# HeadsetR1.net
KiCad netlist of a schematic drawn in EAGLE
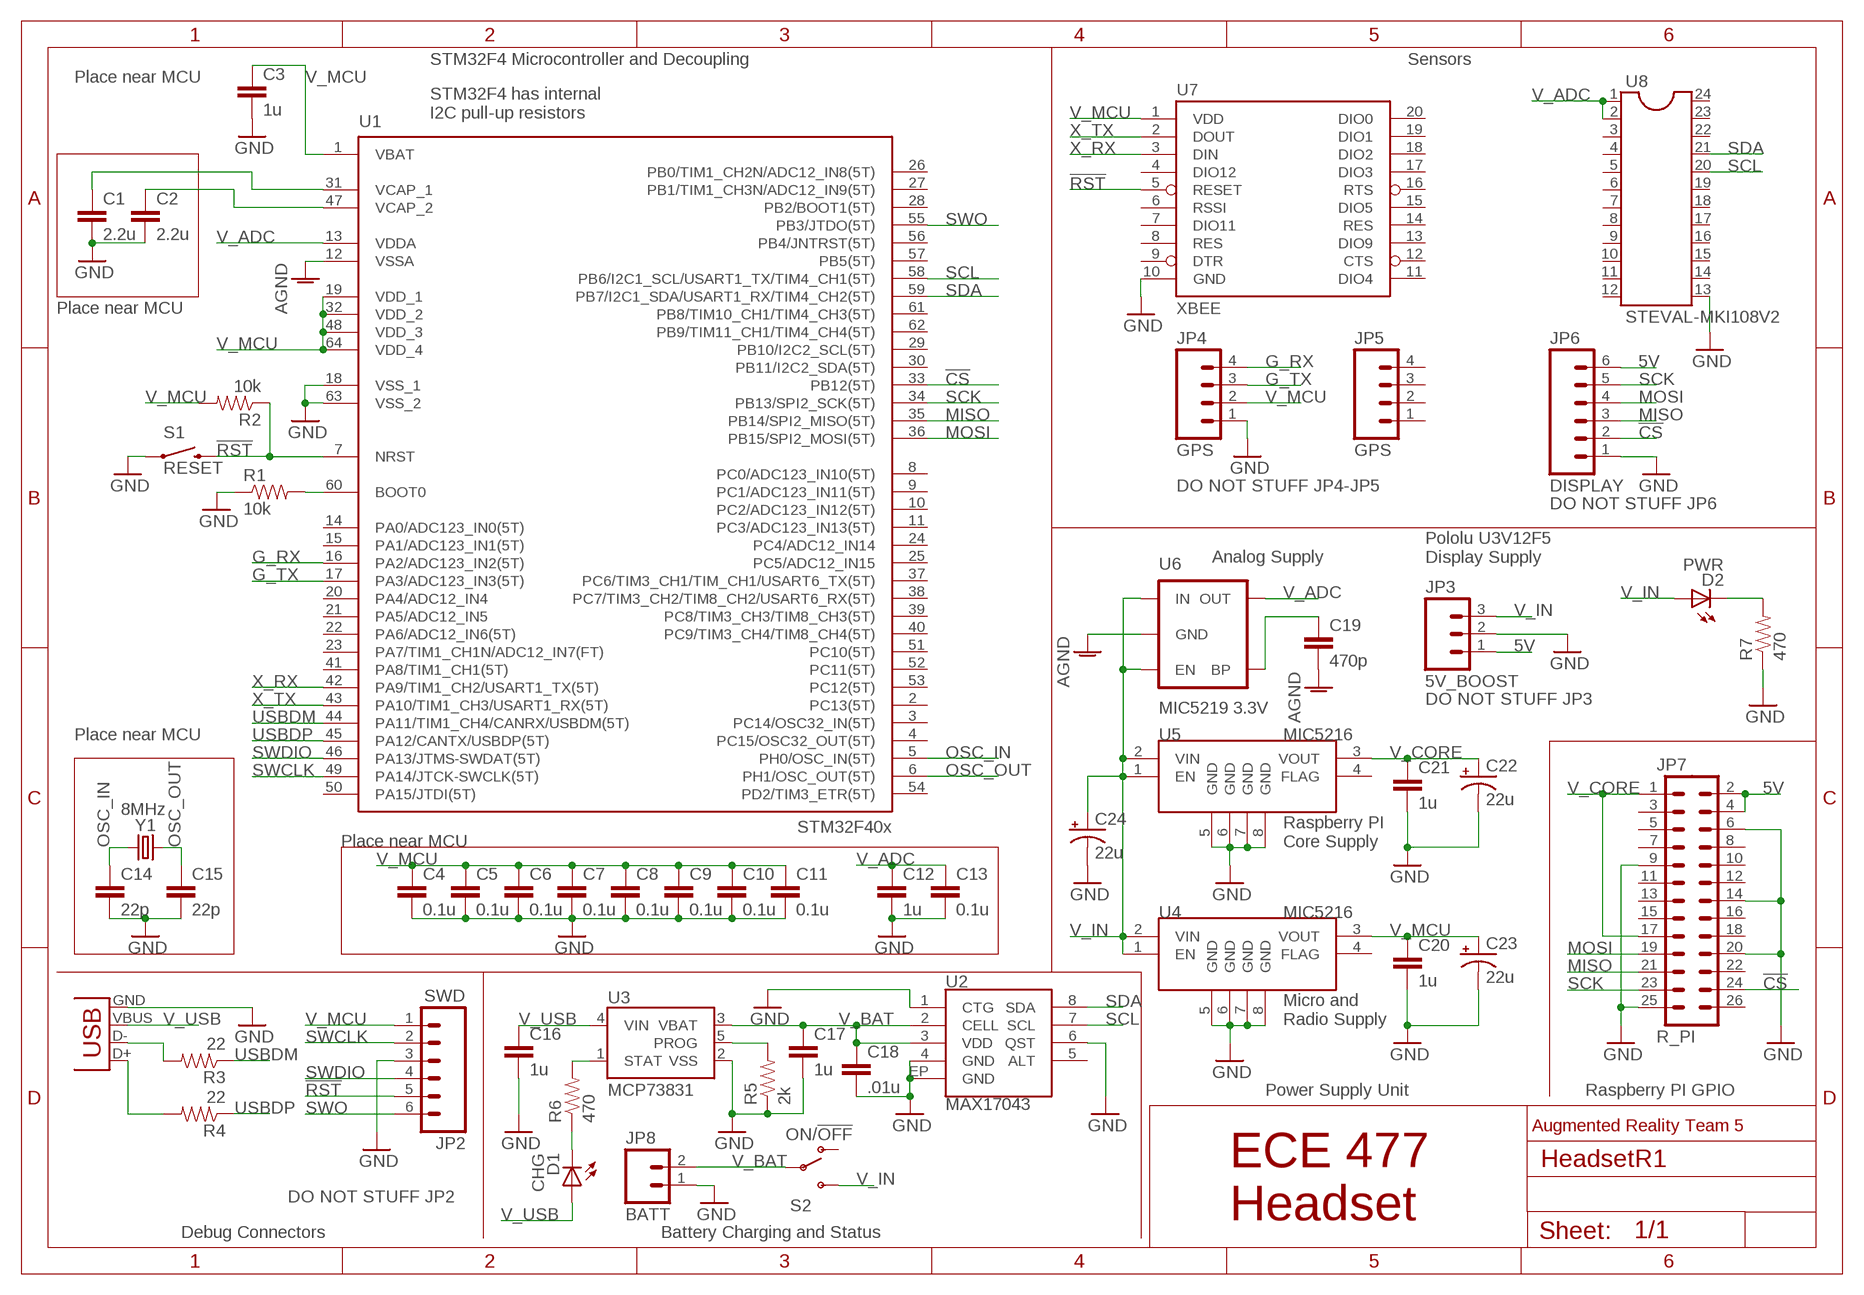
[diagram p0: schematic, sheet 1]

(export (version "E")
  (design (tool "Eeschema 10.0.6"))
  (components
    (comp (ref "C1")
      (value "2.2u")
      (footprint "eagle-import:0805")
      (libsource (lib "eagle-import") (part "CAP0805"))
    )
    (comp (ref "C2")
      (value "2.2u")
      (footprint "eagle-import:0805")
      (libsource (lib "eagle-import") (part "CAP0805"))
    )
    (comp (ref "C3")
      (value "1u")
      (footprint "eagle-import:0805")
      (libsource (lib "eagle-import") (part "CAP0805"))
    )
    (comp (ref "C4")
      (value "0.1u")
      (footprint "eagle-import:0805")
      (libsource (lib "eagle-import") (part "CAP0805"))
    )
    (comp (ref "C5")
      (value "0.1u")
      (footprint "eagle-import:0805")
      (libsource (lib "eagle-import") (part "CAP0805"))
    )
    (comp (ref "C6")
      (value "0.1u")
      (footprint "eagle-import:0805")
      (libsource (lib "eagle-import") (part "CAP0805"))
    )
    (comp (ref "C7")
      (value "0.1u")
      (footprint "eagle-import:0805")
      (libsource (lib "eagle-import") (part "CAP0805"))
    )
    (comp (ref "C8")
      (value "0.1u")
      (footprint "eagle-import:0805")
      (libsource (lib "eagle-import") (part "CAP0805"))
    )
    (comp (ref "C9")
      (value "0.1u")
      (footprint "eagle-import:0805")
      (libsource (lib "eagle-import") (part "CAP0805"))
    )
    (comp (ref "C10")
      (value "0.1u")
      (footprint "eagle-import:0805")
      (libsource (lib "eagle-import") (part "CAP0805"))
    )
    (comp (ref "C11")
      (value "0.1u")
      (footprint "eagle-import:0805")
      (libsource (lib "eagle-import") (part "CAP0805"))
    )
    (comp (ref "C12")
      (value "1u")
      (footprint "eagle-import:0805")
      (libsource (lib "eagle-import") (part "CAP0805"))
    )
    (comp (ref "C13")
      (value "0.1u")
      (footprint "eagle-import:0805")
      (libsource (lib "eagle-import") (part "CAP0805"))
    )
    (comp (ref "C14")
      (value "22p")
      (footprint "eagle-import:0805")
      (libsource (lib "eagle-import") (part "CAP0805"))
    )
    (comp (ref "C15")
      (value "22p")
      (footprint "eagle-import:0805")
      (libsource (lib "eagle-import") (part "CAP0805"))
    )
    (comp (ref "C16")
      (value "1u")
      (footprint "eagle-import:0805")
      (libsource (lib "eagle-import") (part "CAP0805"))
    )
    (comp (ref "C17")
      (value "1u")
      (footprint "eagle-import:0805")
      (libsource (lib "eagle-import") (part "CAP0805"))
    )
    (comp (ref "C18")
      (value ".01u")
      (footprint "eagle-import:0805")
      (libsource (lib "eagle-import") (part "CAP0805"))
    )
    (comp (ref "C19")
      (value "470p")
      (footprint "eagle-import:0805")
      (libsource (lib "eagle-import") (part "CAP0805"))
    )
    (comp (ref "C20")
      (value "1u")
      (footprint "eagle-import:0805")
      (libsource (lib "eagle-import") (part "CAP0805"))
    )
    (comp (ref "C21")
      (value "1u")
      (footprint "eagle-import:0805")
      (libsource (lib "eagle-import") (part "CAP0805"))
    )
    (comp (ref "C22")
      (value "22u")
      (footprint "eagle-import:VISHAY_D")
      (libsource (lib "eagle-import") (part "CAP_POLVISHAY_D"))
    )
    (comp (ref "C23")
      (value "22u")
      (footprint "eagle-import:VISHAY_D")
      (libsource (lib "eagle-import") (part "CAP_POLVISHAY_D"))
    )
    (comp (ref "C24")
      (value "22u")
      (footprint "eagle-import:VISHAY_D")
      (libsource (lib "eagle-import") (part "CAP_POLVISHAY_D"))
    )
    (comp (ref "D1")
      (value "CHG")
      (footprint "eagle-import:LED-1206")
      (libsource (lib "eagle-import") (part "LED-RED1206"))
    )
    (comp (ref "D2")
      (value "PWR")
      (footprint "eagle-import:LED-1206")
      (libsource (lib "eagle-import") (part "LED-RED1206"))
    )
    (comp (ref "JP1")
      (value "USBSMD")
      (footprint "eagle-import:USB-MINIB")
      (libsource (lib "eagle-import") (part "USBSMD"))
    )
    (comp (ref "JP2")
      (value "SWD")
      (footprint "eagle-import:1X06")
      (libsource (lib "eagle-import") (part "M06SIP"))
    )
    (comp (ref "JP3")
      (value "5V_BOOST")
      (footprint "eagle-import:1X03")
      (libsource (lib "eagle-import") (part "M03PTH"))
    )
    (comp (ref "JP4")
      (value "GPS")
      (footprint "eagle-import:1X04")
      (libsource (lib "eagle-import") (part "M04PTH"))
    )
    (comp (ref "JP5")
      (value "GPS")
      (footprint "eagle-import:1X04")
      (libsource (lib "eagle-import") (part "M04PTH"))
    )
    (comp (ref "JP6")
      (value "DISPLAY")
      (footprint "eagle-import:1X06")
      (libsource (lib "eagle-import") (part "M06SIP"))
    )
    (comp (ref "JP7")
      (value "R_PI")
      (footprint "eagle-import:2X13")
      (libsource (lib "eagle-import") (part "M13X22X13"))
    )
    (comp (ref "JP8")
      (value "BATT")
      (footprint "eagle-import:JST-2-PTH")
      (libsource (lib "eagle-import") (part "M02JST-PTH-2"))
    )
    (comp (ref "R1")
      (value "10k")
      (footprint "eagle-import:0805")
      (libsource (lib "eagle-import") (part "RES"))
    )
    (comp (ref "R2")
      (value "10k")
      (footprint "eagle-import:0805")
      (libsource (lib "eagle-import") (part "RES"))
    )
    (comp (ref "R3")
      (value "22")
      (footprint "eagle-import:0805")
      (libsource (lib "eagle-import") (part "RES"))
    )
    (comp (ref "R4")
      (value "22")
      (footprint "eagle-import:0805")
      (libsource (lib "eagle-import") (part "RES"))
    )
    (comp (ref "R5")
      (value "2k")
      (footprint "eagle-import:0805")
      (libsource (lib "eagle-import") (part "RES"))
    )
    (comp (ref "R6")
      (value "470")
      (footprint "eagle-import:0805")
      (libsource (lib "eagle-import") (part "RES"))
    )
    (comp (ref "R7")
      (value "470")
      (footprint "eagle-import:0805")
      (libsource (lib "eagle-import") (part "RES"))
    )
    (comp (ref "S1")
      (value "RESET")
      (footprint "eagle-import:TACTILE-PTH")
      (libsource (lib "eagle-import") (part "SWITCH-MOMENTARY-2PTH"))
    )
    (comp (ref "S2")
      (value "ON/!OFF!")
      (footprint "eagle-import:SWITCH-SPDT")
      (libsource (lib "eagle-import") (part "SWITCH-SPDTPTH"))
    )
    (comp (ref "U1")
      (value "STM32F405RGT6")
      (footprint "eagle-import:TQFP64")
      (libsource (lib "eagle-import") (part "STM32F405R"))
    )
    (comp (ref "U2")
      (value "MAX17043")
      (footprint "eagle-import:TDFN-8")
      (libsource (lib "eagle-import") (part "MAX1704X"))
    )
    (comp (ref "U3")
      (value "MCP73831")
      (footprint "eagle-import:SOT23-5")
      (libsource (lib "eagle-import") (part "MCP73831"))
    )
    (comp (ref "U4")
      (value "MIC5216")
      (footprint "eagle-import:MSOP8")
      (libsource (lib "eagle-import") (part "V_REG_MIC5216"))
    )
    (comp (ref "U5")
      (value "MIC5216")
      (footprint "eagle-import:MSOP8")
      (libsource (lib "eagle-import") (part "V_REG_MIC5216"))
    )
    (comp (ref "U6")
      (value "MIC5219 3.3V")
      (footprint "eagle-import:SOT23-5")
      (libsource (lib "eagle-import") (part "V_REG_MIC52193.3V"))
    )
    (comp (ref "U7")
      (value "XBEE")
      (footprint "eagle-import:XBEE-1")
      (libsource (lib "eagle-import") (part "XBEE-1B1"))
    )
    (comp (ref "U8")
      (value "STEVAL-MKI108V2")
      (footprint "eagle-import:DIL24-6")
      (libsource (lib "eagle-import") (part "DIL24-6"))
    )
    (comp (ref "Y1")
      (value "8MHz")
      (footprint "eagle-import:HC49UP")
      (libsource (lib "eagle-import") (part "CRYSTALSMD"))
    )
  )
  (nets
    (net (code "1") (name "/5V") (class "Default")
      (node (ref "JP3") (pin "1") (pinfunction "1_1") (pintype "passive"))
      (node (ref "JP6") (pin "6") (pinfunction "6_6") (pintype "passive"))
      (node (ref "JP7") (pin "2") (pinfunction "2_2") (pintype "passive"))
      (node (ref "JP7") (pin "4") (pinfunction "4_4") (pintype "passive"))
    )
    (net (code "2") (name "/G_RX") (class "Default")
      (node (ref "JP4") (pin "4") (pinfunction "4_4") (pintype "passive"))
      (node (ref "U1") (pin "16") (pinfunction "PA2/ADC123_IN2(5T)_16") (pintype "bidirectional"))
    )
    (net (code "3") (name "/G_TX") (class "Default")
      (node (ref "JP4") (pin "3") (pinfunction "3_3") (pintype "passive"))
      (node (ref "U1") (pin "17") (pinfunction "PA3/ADC123_IN3(5T)_17") (pintype "bidirectional"))
    )
    (net (code "4") (name "/MISO") (class "Default")
      (node (ref "JP6") (pin "3") (pinfunction "3_3") (pintype "passive"))
      (node (ref "JP7") (pin "21") (pinfunction "21_21") (pintype "passive"))
      (node (ref "U1") (pin "35") (pinfunction "PB14/SPI2_MISO(5T)_35") (pintype "bidirectional"))
    )
    (net (code "5") (name "/MOSI") (class "Default")
      (node (ref "JP6") (pin "4") (pinfunction "4_4") (pintype "passive"))
      (node (ref "JP7") (pin "19") (pinfunction "19_19") (pintype "passive"))
      (node (ref "U1") (pin "36") (pinfunction "PB15/SPI2_MOSI(5T)_36") (pintype "bidirectional"))
    )
    (net (code "6") (name "/OSC_IN") (class "Default")
      (node (ref "C14") (pin "1") (pinfunction "1_1") (pintype "passive"))
      (node (ref "U1") (pin "5") (pinfunction "PH0/OSC_IN(5T)_5") (pintype "bidirectional"))
      (node (ref "Y1") (pin "1") (pinfunction "1_1") (pintype "passive"))
    )
    (net (code "7") (name "/OSC_OUT") (class "Default")
      (node (ref "C15") (pin "1") (pinfunction "1_1") (pintype "passive"))
      (node (ref "U1") (pin "6") (pinfunction "PH1/OSC_OUT(5T)_6") (pintype "bidirectional"))
      (node (ref "Y1") (pin "2") (pinfunction "2_2") (pintype "passive"))
    )
    (net (code "8") (name "/SCK") (class "Default")
      (node (ref "JP6") (pin "5") (pinfunction "5_5") (pintype "passive"))
      (node (ref "JP7") (pin "23") (pinfunction "23_23") (pintype "passive"))
      (node (ref "U1") (pin "34") (pinfunction "PB13/SPI2_SCK(5T)_34") (pintype "bidirectional"))
    )
    (net (code "9") (name "/SCL") (class "Default")
      (node (ref "U1") (pin "58") (pinfunction "PB6/I2C1_SCL/USART1_TX/TIM4_CH1(5T)_58") (pintype "bidirectional"))
      (node (ref "U2") (pin "7") (pinfunction "SCL_7") (pintype "bidirectional"))
      (node (ref "U8") (pin "20") (pinfunction "20_20") (pintype "passive"))
    )
    (net (code "10") (name "/SDA") (class "Default")
      (node (ref "U1") (pin "59") (pinfunction "PB7/I2C1_SDA/USART1_RX/TIM4_CH2(5T)_59") (pintype "bidirectional"))
      (node (ref "U2") (pin "8") (pinfunction "SDA_8") (pintype "bidirectional"))
      (node (ref "U8") (pin "21") (pinfunction "21_21") (pintype "passive"))
    )
    (net (code "11") (name "/SWCLK") (class "Default")
      (node (ref "JP2") (pin "2") (pinfunction "2_2") (pintype "passive"))
      (node (ref "U1") (pin "49") (pinfunction "PA14/JTCK-SWCLK(5T)_49") (pintype "bidirectional"))
    )
    (net (code "12") (name "/SWDIO") (class "Default")
      (node (ref "JP2") (pin "4") (pinfunction "4_4") (pintype "passive"))
      (node (ref "U1") (pin "46") (pinfunction "PA13/JTMS-SWDAT(5T)_46") (pintype "bidirectional"))
    )
    (net (code "13") (name "/SWO") (class "Default")
      (node (ref "JP2") (pin "6") (pinfunction "6_6") (pintype "passive"))
      (node (ref "U1") (pin "55") (pinfunction "PB3/JTDO(5T)_55") (pintype "bidirectional"))
    )
    (net (code "14") (name "/USBDM") (class "Default")
      (node (ref "R3") (pin "1") (pinfunction "1_1") (pintype "passive"))
      (node (ref "U1") (pin "44") (pinfunction "PA11/TIM1_CH4/CANRX/USBDM(5T)_44") (pintype "bidirectional"))
    )
    (net (code "15") (name "/USBDP") (class "Default")
      (node (ref "R4") (pin "1") (pinfunction "1_1") (pintype "passive"))
      (node (ref "U1") (pin "45") (pinfunction "PA12/CANTX/USBDP(5T)_45") (pintype "bidirectional"))
    )
    (net (code "16") (name "/V_ADC") (class "Default")
      (node (ref "C12") (pin "1") (pinfunction "1_1") (pintype "passive"))
      (node (ref "C13") (pin "1") (pinfunction "1_1") (pintype "passive"))
      (node (ref "U1") (pin "13") (pinfunction "VDDA_13") (pintype "bidirectional"))
      (node (ref "U6") (pin "5") (pinfunction "OUT_5") (pintype "passive"))
      (node (ref "U8") (pin "1") (pinfunction "1_1") (pintype "passive"))
      (node (ref "U8") (pin "2") (pinfunction "2_2") (pintype "passive"))
    )
    (net (code "17") (name "/V_BAT") (class "Default")
      (node (ref "C17") (pin "1") (pinfunction "1_1") (pintype "passive"))
      (node (ref "C18") (pin "1") (pinfunction "1_1") (pintype "passive"))
      (node (ref "JP8") (pin "2") (pinfunction "2_2") (pintype "passive"))
      (node (ref "S2") (pin "2") (pinfunction "P_2") (pintype "passive"))
      (node (ref "U2") (pin "2") (pinfunction "CELL_2") (pintype "bidirectional"))
      (node (ref "U2") (pin "3") (pinfunction "VDD_3") (pintype "bidirectional"))
      (node (ref "U3") (pin "3") (pinfunction "VBAT_3") (pintype "power_in"))
    )
    (net (code "18") (name "/V_CORE") (class "Default")
      (node (ref "C21") (pin "1") (pinfunction "1_1") (pintype "passive"))
      (node (ref "C22") (pin "+") (pinfunction "+_+") (pintype "passive"))
      (node (ref "JP7") (pin "1") (pinfunction "1_1") (pintype "passive"))
      (node (ref "JP7") (pin "17") (pinfunction "17_17") (pintype "passive"))
      (node (ref "U5") (pin "3") (pinfunction "VOUT_3") (pintype "bidirectional"))
    )
    (net (code "19") (name "/V_IN") (class "Default")
      (node (ref "C24") (pin "+") (pinfunction "+_+") (pintype "passive"))
      (node (ref "D2") (pin "A") (pinfunction "A_A") (pintype "passive"))
      (node (ref "JP3") (pin "3") (pinfunction "3_3") (pintype "passive"))
      (node (ref "S2") (pin "3") (pinfunction "S_3") (pintype "passive"))
      (node (ref "U4") (pin "1") (pinfunction "EN_1") (pintype "bidirectional"))
      (node (ref "U4") (pin "2") (pinfunction "VIN_2") (pintype "bidirectional"))
      (node (ref "U5") (pin "1") (pinfunction "EN_1") (pintype "bidirectional"))
      (node (ref "U5") (pin "2") (pinfunction "VIN_2") (pintype "bidirectional"))
      (node (ref "U6") (pin "1") (pinfunction "IN_1") (pintype "input"))
      (node (ref "U6") (pin "3") (pinfunction "EN_3") (pintype "input"))
    )
    (net (code "20") (name "/V_MCU") (class "Default")
      (node (ref "C10") (pin "1") (pinfunction "1_1") (pintype "passive"))
      (node (ref "C11") (pin "1") (pinfunction "1_1") (pintype "passive"))
      (node (ref "C20") (pin "1") (pinfunction "1_1") (pintype "passive"))
      (node (ref "C23") (pin "+") (pinfunction "+_+") (pintype "passive"))
      (node (ref "C3") (pin "1") (pinfunction "1_1") (pintype "passive"))
      (node (ref "C4") (pin "1") (pinfunction "1_1") (pintype "passive"))
      (node (ref "C5") (pin "1") (pinfunction "1_1") (pintype "passive"))
      (node (ref "C6") (pin "1") (pinfunction "1_1") (pintype "passive"))
      (node (ref "C7") (pin "1") (pinfunction "1_1") (pintype "passive"))
      (node (ref "C8") (pin "1") (pinfunction "1_1") (pintype "passive"))
      (node (ref "C9") (pin "1") (pinfunction "1_1") (pintype "passive"))
      (node (ref "JP2") (pin "1") (pinfunction "1_1") (pintype "passive"))
      (node (ref "JP4") (pin "2") (pinfunction "2_2") (pintype "passive"))
      (node (ref "R2") (pin "2") (pinfunction "2_2") (pintype "passive"))
      (node (ref "U1") (pin "1") (pinfunction "VBAT_1") (pintype "bidirectional"))
      (node (ref "U1") (pin "19") (pinfunction "VDD_1_19") (pintype "bidirectional"))
      (node (ref "U1") (pin "32") (pinfunction "VDD_2_32") (pintype "bidirectional"))
      (node (ref "U1") (pin "48") (pinfunction "VDD_3_48") (pintype "bidirectional"))
      (node (ref "U1") (pin "64") (pinfunction "VDD_4_64") (pintype "bidirectional"))
      (node (ref "U4") (pin "3") (pinfunction "VOUT_3") (pintype "bidirectional"))
      (node (ref "U7") (pin "1") (pinfunction "VDD_1") (pintype "power_in"))
    )
    (net (code "21") (name "/V_USB") (class "Default")
      (node (ref "C16") (pin "1") (pinfunction "1_1") (pintype "passive"))
      (node (ref "D1") (pin "A") (pinfunction "A_A") (pintype "passive"))
      (node (ref "JP1") (pin "VBUS") (pinfunction "VBUS_VBUS") (pintype "bidirectional"))
      (node (ref "U3") (pin "4") (pinfunction "VIN_4") (pintype "power_in"))
    )
    (net (code "22") (name "/X_RX") (class "Default")
      (node (ref "U1") (pin "42") (pinfunction "PA9/TIM1_CH2/USART1_TX(5T)_42") (pintype "bidirectional"))
      (node (ref "U7") (pin "3") (pinfunction "DIN_3") (pintype "input"))
    )
    (net (code "23") (name "/X_TX") (class "Default")
      (node (ref "U1") (pin "43") (pinfunction "PA10/TIM1_CH3/USART1_RX(5T)_43") (pintype "bidirectional"))
      (node (ref "U7") (pin "2") (pinfunction "DOUT_2") (pintype "output"))
    )
    (net (code "24") (name "/~{CS}") (class "Default")
      (node (ref "JP6") (pin "2") (pinfunction "2_2") (pintype "passive"))
      (node (ref "JP7") (pin "24") (pinfunction "24_24") (pintype "passive"))
      (node (ref "U1") (pin "33") (pinfunction "PB12(5T)_33") (pintype "bidirectional"))
    )
    (net (code "25") (name "/~{RST}") (class "Default")
      (node (ref "JP2") (pin "5") (pinfunction "5_5") (pintype "passive"))
      (node (ref "R2") (pin "1") (pinfunction "1_1") (pintype "passive"))
      (node (ref "S1") (pin "3") (pinfunction "2_3") (pintype "passive"))
      (node (ref "U1") (pin "7") (pinfunction "NRST_7") (pintype "bidirectional"))
      (node (ref "U7") (pin "5") (pinfunction "RESET_5") (pintype "input"))
    )
    (net (code "26") (name "AGND") (class "Default")
      (node (ref "C19") (pin "2") (pinfunction "2_2") (pintype "passive"))
      (node (ref "U1") (pin "12") (pinfunction "VSSA_12") (pintype "bidirectional"))
      (node (ref "U6") (pin "2") (pinfunction "GND_2") (pintype "input"))
    )
    (net (code "27") (name "GND") (class "Default")
      (node (ref "C1") (pin "2") (pinfunction "2_2") (pintype "passive"))
      (node (ref "C10") (pin "2") (pinfunction "2_2") (pintype "passive"))
      (node (ref "C11") (pin "2") (pinfunction "2_2") (pintype "passive"))
      (node (ref "C12") (pin "2") (pinfunction "2_2") (pintype "passive"))
      (node (ref "C13") (pin "2") (pinfunction "2_2") (pintype "passive"))
      (node (ref "C14") (pin "2") (pinfunction "2_2") (pintype "passive"))
      (node (ref "C15") (pin "2") (pinfunction "2_2") (pintype "passive"))
      (node (ref "C16") (pin "2") (pinfunction "2_2") (pintype "passive"))
      (node (ref "C17") (pin "2") (pinfunction "2_2") (pintype "passive"))
      (node (ref "C18") (pin "2") (pinfunction "2_2") (pintype "passive"))
      (node (ref "C2") (pin "2") (pinfunction "2_2") (pintype "passive"))
      (node (ref "C20") (pin "2") (pinfunction "2_2") (pintype "passive"))
      (node (ref "C21") (pin "2") (pinfunction "2_2") (pintype "passive"))
      (node (ref "C22") (pin "-") (pinfunction "-_-") (pintype "passive"))
      (node (ref "C23") (pin "-") (pinfunction "-_-") (pintype "passive"))
      (node (ref "C24") (pin "-") (pinfunction "-_-") (pintype "passive"))
      (node (ref "C3") (pin "2") (pinfunction "2_2") (pintype "passive"))
      (node (ref "C4") (pin "2") (pinfunction "2_2") (pintype "passive"))
      (node (ref "C5") (pin "2") (pinfunction "2_2") (pintype "passive"))
      (node (ref "C6") (pin "2") (pinfunction "2_2") (pintype "passive"))
      (node (ref "C7") (pin "2") (pinfunction "2_2") (pintype "passive"))
      (node (ref "C8") (pin "2") (pinfunction "2_2") (pintype "passive"))
      (node (ref "C9") (pin "2") (pinfunction "2_2") (pintype "passive"))
      (node (ref "JP1") (pin "GND") (pinfunction "GND_GND") (pintype "bidirectional"))
      (node (ref "JP2") (pin "3") (pinfunction "3_3") (pintype "passive"))
      (node (ref "JP3") (pin "2") (pinfunction "2_2") (pintype "passive"))
      (node (ref "JP4") (pin "1") (pinfunction "1_1") (pintype "passive"))
      (node (ref "JP6") (pin "1") (pinfunction "1_1") (pintype "passive"))
      (node (ref "JP7") (pin "14") (pinfunction "14_14") (pintype "passive"))
      (node (ref "JP7") (pin "20") (pinfunction "20_20") (pintype "passive"))
      (node (ref "JP7") (pin "25") (pinfunction "25_25") (pintype "passive"))
      (node (ref "JP7") (pin "6") (pinfunction "6_6") (pintype "passive"))
      (node (ref "JP7") (pin "9") (pinfunction "9_9") (pintype "passive"))
      (node (ref "JP8") (pin "1") (pinfunction "1_1") (pintype "passive"))
      (node (ref "R1") (pin "1") (pinfunction "1_1") (pintype "passive"))
      (node (ref "R5") (pin "1") (pinfunction "1_1") (pintype "passive"))
      (node (ref "R7") (pin "1") (pinfunction "1_1") (pintype "passive"))
      (node (ref "S1") (pin "1") (pinfunction "1_1") (pintype "passive"))
      (node (ref "U1") (pin "18") (pinfunction "VSS_1_18") (pintype "bidirectional"))
      (node (ref "U1") (pin "63") (pinfunction "VSS_2_63") (pintype "bidirectional"))
      (node (ref "U2") (pin "1") (pinfunction "CTG_1") (pintype "bidirectional"))
      (node (ref "U2") (pin "4") (pinfunction "GND_4") (pintype "bidirectional"))
      (node (ref "U2") (pin "6") (pinfunction "QST_6") (pintype "bidirectional"))
      (node (ref "U2") (pin "EP") (pinfunction "GND_EP") (pintype "bidirectional"))
      (node (ref "U3") (pin "2") (pinfunction "VSS_2") (pintype "power_in"))
      (node (ref "U4") (pin "5") (pinfunction "GND_5") (pintype "bidirectional"))
      (node (ref "U4") (pin "6") (pinfunction "GND_6") (pintype "bidirectional"))
      (node (ref "U4") (pin "7") (pinfunction "GND_7") (pintype "bidirectional"))
      (node (ref "U4") (pin "8") (pinfunction "GND_8") (pintype "bidirectional"))
      (node (ref "U5") (pin "5") (pinfunction "GND_5") (pintype "bidirectional"))
      (node (ref "U5") (pin "6") (pinfunction "GND_6") (pintype "bidirectional"))
      (node (ref "U5") (pin "7") (pinfunction "GND_7") (pintype "bidirectional"))
      (node (ref "U5") (pin "8") (pinfunction "GND_8") (pintype "bidirectional"))
      (node (ref "U7") (pin "10") (pinfunction "GND_10") (pintype "power_in"))
      (node (ref "U8") (pin "13") (pinfunction "13_13") (pintype "passive"))
    )
    (net (code "28") (name "Net-(D1-PadC)") (class "Default")
      (node (ref "D1") (pin "C") (pinfunction "C_C") (pintype "passive"))
      (node (ref "R6") (pin "1") (pinfunction "1_1") (pintype "passive"))
    )
    (net (code "29") (name "Net-(D2-PadC)") (class "Default")
      (node (ref "D2") (pin "C") (pinfunction "C_C") (pintype "passive"))
      (node (ref "R7") (pin "2") (pinfunction "2_2") (pintype "passive"))
    )
    (net (code "30") (name "Net-(JP1-PadD+)") (class "Default")
      (node (ref "JP1") (pin "D+") (pinfunction "D+_D+") (pintype "bidirectional"))
      (node (ref "R4") (pin "2") (pinfunction "2_2") (pintype "passive"))
    )
    (net (code "31") (name "Net-(JP1-PadD-)") (class "Default")
      (node (ref "JP1") (pin "D-") (pinfunction "D-_D-") (pintype "bidirectional"))
      (node (ref "R3") (pin "2") (pinfunction "2_2") (pintype "passive"))
    )
    (net (code "32") (name "Net-(U1-BOOT0)") (class "Default")
      (node (ref "R1") (pin "2") (pinfunction "2_2") (pintype "passive"))
      (node (ref "U1") (pin "60") (pinfunction "BOOT0_60") (pintype "bidirectional"))
    )
    (net (code "33") (name "Net-(U1-VCAP_1)") (class "Default")
      (node (ref "C1") (pin "1") (pinfunction "1_1") (pintype "passive"))
      (node (ref "U1") (pin "31") (pinfunction "VCAP_1_31") (pintype "bidirectional"))
    )
    (net (code "34") (name "Net-(U1-VCAP_2)") (class "Default")
      (node (ref "C2") (pin "1") (pinfunction "1_1") (pintype "passive"))
      (node (ref "U1") (pin "47") (pinfunction "VCAP_2_47") (pintype "bidirectional"))
    )
    (net (code "35") (name "Net-(U3-PROG)") (class "Default")
      (node (ref "R5") (pin "2") (pinfunction "2_2") (pintype "passive"))
      (node (ref "U3") (pin "5") (pinfunction "PROG_5") (pintype "input"))
    )
    (net (code "36") (name "Net-(U3-STAT)") (class "Default")
      (node (ref "R6") (pin "2") (pinfunction "2_2") (pintype "passive"))
      (node (ref "U3") (pin "1") (pinfunction "STAT_1") (pintype "output"))
    )
    (net (code "37") (name "Net-(U6-BP)") (class "Default")
      (node (ref "C19") (pin "1") (pinfunction "1_1") (pintype "passive"))
      (node (ref "U6") (pin "4") (pinfunction "BP_4") (pintype "input"))
    )
    (net (code "38") (name "unconnected-(JP5-Pad1)") (class "Default")
      (node (ref "JP5") (pin "1") (pinfunction "1_1") (pintype "passive"))
    )
    (net (code "39") (name "unconnected-(JP5-Pad2)") (class "Default")
      (node (ref "JP5") (pin "2") (pinfunction "2_2") (pintype "passive"))
    )
    (net (code "40") (name "unconnected-(JP5-Pad3)") (class "Default")
      (node (ref "JP5") (pin "3") (pinfunction "3_3") (pintype "passive"))
    )
    (net (code "41") (name "unconnected-(JP5-Pad4)") (class "Default")
      (node (ref "JP5") (pin "4") (pinfunction "4_4") (pintype "passive"))
    )
    (net (code "42") (name "unconnected-(JP7-Pad3)") (class "Default")
      (node (ref "JP7") (pin "3") (pinfunction "3_3") (pintype "passive"))
    )
    (net (code "43") (name "unconnected-(JP7-Pad5)") (class "Default")
      (node (ref "JP7") (pin "5") (pinfunction "5_5") (pintype "passive"))
    )
    (net (code "44") (name "unconnected-(JP7-Pad7)") (class "Default")
      (node (ref "JP7") (pin "7") (pinfunction "7_7") (pintype "passive"))
    )
    (net (code "45") (name "unconnected-(JP7-Pad8)") (class "Default")
      (node (ref "JP7") (pin "8") (pinfunction "8_8") (pintype "passive"))
    )
    (net (code "46") (name "unconnected-(JP7-Pad10)") (class "Default")
      (node (ref "JP7") (pin "10") (pinfunction "10_10") (pintype "passive"))
    )
    (net (code "47") (name "unconnected-(JP7-Pad11)") (class "Default")
      (node (ref "JP7") (pin "11") (pinfunction "11_11") (pintype "passive"))
    )
    (net (code "48") (name "unconnected-(JP7-Pad12)") (class "Default")
      (node (ref "JP7") (pin "12") (pinfunction "12_12") (pintype "passive"))
    )
    (net (code "49") (name "unconnected-(JP7-Pad13)") (class "Default")
      (node (ref "JP7") (pin "13") (pinfunction "13_13") (pintype "passive"))
    )
    (net (code "50") (name "unconnected-(JP7-Pad15)") (class "Default")
      (node (ref "JP7") (pin "15") (pinfunction "15_15") (pintype "passive"))
    )
    (net (code "51") (name "unconnected-(JP7-Pad16)") (class "Default")
      (node (ref "JP7") (pin "16") (pinfunction "16_16") (pintype "passive"))
    )
    (net (code "52") (name "unconnected-(JP7-Pad18)") (class "Default")
      (node (ref "JP7") (pin "18") (pinfunction "18_18") (pintype "passive"))
    )
    (net (code "53") (name "unconnected-(JP7-Pad22)") (class "Default")
      (node (ref "JP7") (pin "22") (pinfunction "22_22") (pintype "passive"))
    )
    (net (code "54") (name "unconnected-(JP7-Pad26)") (class "Default")
      (node (ref "JP7") (pin "26") (pinfunction "26_26") (pintype "passive"))
    )
    (net (code "55") (name "unconnected-(S2-O-Pad1)") (class "Default")
      (node (ref "S2") (pin "1") (pinfunction "O_1") (pintype "passive"))
    )
    (net (code "56") (name "unconnected-(U1-PA0{slash}ADC123_IN0(5T)-Pad14)") (class "Default")
      (node (ref "U1") (pin "14") (pinfunction "PA0/ADC123_IN0(5T)_14") (pintype "bidirectional"))
    )
    (net (code "57") (name "unconnected-(U1-PA1{slash}ADC123_IN1(5T)-Pad15)") (class "Default")
      (node (ref "U1") (pin "15") (pinfunction "PA1/ADC123_IN1(5T)_15") (pintype "bidirectional"))
    )
    (net (code "58") (name "unconnected-(U1-PA4{slash}ADC12_IN4-Pad20)") (class "Default")
      (node (ref "U1") (pin "20") (pinfunction "PA4/ADC12_IN4_20") (pintype "bidirectional"))
    )
    (net (code "59") (name "unconnected-(U1-PA5{slash}ADC12_IN5-Pad21)") (class "Default")
      (node (ref "U1") (pin "21") (pinfunction "PA5/ADC12_IN5_21") (pintype "bidirectional"))
    )
    (net (code "60") (name "unconnected-(U1-PA6{slash}ADC12_IN6(5T)-Pad22)") (class "Default")
      (node (ref "U1") (pin "22") (pinfunction "PA6/ADC12_IN6(5T)_22") (pintype "bidirectional"))
    )
    (net (code "61") (name "unconnected-(U1-PA7{slash}TIM1_CH1N{slash}ADC12_IN7(FT)-Pad23)") (class "Default")
      (node (ref "U1") (pin "23") (pinfunction "PA7/TIM1_CH1N/ADC12_IN7(FT)_23") (pintype "bidirectional"))
    )
    (net (code "62") (name "unconnected-(U1-PA8{slash}TIM1_CH1(5T)-Pad41)") (class "Default")
      (node (ref "U1") (pin "41") (pinfunction "PA8/TIM1_CH1(5T)_41") (pintype "bidirectional"))
    )
    (net (code "63") (name "unconnected-(U1-PA15{slash}JTDI(5T)-Pad50)") (class "Default")
      (node (ref "U1") (pin "50") (pinfunction "PA15/JTDI(5T)_50") (pintype "bidirectional"))
    )
    (net (code "64") (name "unconnected-(U1-PB0{slash}TIM1_CH2N{slash}ADC12_IN8(5T)-Pad26)") (class "Default")
      (node (ref "U1") (pin "26") (pinfunction "PB0/TIM1_CH2N/ADC12_IN8(5T)_26") (pintype "bidirectional"))
    )
    (net (code "65") (name "unconnected-(U1-PB1{slash}TIM1_CH3N{slash}ADC12_IN9(5T)-Pad27)") (class "Default")
      (node (ref "U1") (pin "27") (pinfunction "PB1/TIM1_CH3N/ADC12_IN9(5T)_27") (pintype "bidirectional"))
    )
    (net (code "66") (name "unconnected-(U1-PB2{slash}BOOT1(5T)-Pad28)") (class "Default")
      (node (ref "U1") (pin "28") (pinfunction "PB2/BOOT1(5T)_28") (pintype "bidirectional"))
    )
    (net (code "67") (name "unconnected-(U1-PB4{slash}JNTRST(5T)-Pad56)") (class "Default")
      (node (ref "U1") (pin "56") (pinfunction "PB4/JNTRST(5T)_56") (pintype "bidirectional"))
    )
    (net (code "68") (name "unconnected-(U1-PB5(5T)-Pad57)") (class "Default")
      (node (ref "U1") (pin "57") (pinfunction "PB5(5T)_57") (pintype "bidirectional"))
    )
    (net (code "69") (name "unconnected-(U1-PB8{slash}TIM10_CH1{slash}TIM4_CH3(5T)-Pad61)") (class "Default")
      (node (ref "U1") (pin "61") (pinfunction "PB8/TIM10_CH1/TIM4_CH3(5T)_61") (pintype "bidirectional"))
    )
    (net (code "70") (name "unconnected-(U1-PB9{slash}TIM11_CH1{slash}TIM4_CH4(5T)-Pad62)") (class "Default")
      (node (ref "U1") (pin "62") (pinfunction "PB9/TIM11_CH1/TIM4_CH4(5T)_62") (pintype "bidirectional"))
    )
    (net (code "71") (name "unconnected-(U1-PB10{slash}I2C2_SCL(5T)-Pad29)") (class "Default")
      (node (ref "U1") (pin "29") (pinfunction "PB10/I2C2_SCL(5T)_29") (pintype "bidirectional"))
    )
    (net (code "72") (name "unconnected-(U1-PB11{slash}I2C2_SDA(5T)-Pad30)") (class "Default")
      (node (ref "U1") (pin "30") (pinfunction "PB11/I2C2_SDA(5T)_30") (pintype "bidirectional"))
    )
    (net (code "73") (name "unconnected-(U1-PC0{slash}ADC123_IN10(5T)-Pad8)") (class "Default")
      (node (ref "U1") (pin "8") (pinfunction "PC0/ADC123_IN10(5T)_8") (pintype "bidirectional"))
    )
    (net (code "74") (name "unconnected-(U1-PC1{slash}ADC123_IN11(5T)-Pad9)") (class "Default")
      (node (ref "U1") (pin "9") (pinfunction "PC1/ADC123_IN11(5T)_9") (pintype "bidirectional"))
    )
    (net (code "75") (name "unconnected-(U1-PC2{slash}ADC123_IN12(5T)-Pad10)") (class "Default")
      (node (ref "U1") (pin "10") (pinfunction "PC2/ADC123_IN12(5T)_10") (pintype "bidirectional"))
    )
    (net (code "76") (name "unconnected-(U1-PC3{slash}ADC123_IN13(5T)-Pad11)") (class "Default")
      (node (ref "U1") (pin "11") (pinfunction "PC3/ADC123_IN13(5T)_11") (pintype "bidirectional"))
    )
    (net (code "77") (name "unconnected-(U1-PC4{slash}ADC12_IN14-Pad24)") (class "Default")
      (node (ref "U1") (pin "24") (pinfunction "PC4/ADC12_IN14_24") (pintype "bidirectional"))
    )
    (net (code "78") (name "unconnected-(U1-PC5{slash}ADC12_IN15-Pad25)") (class "Default")
      (node (ref "U1") (pin "25") (pinfunction "PC5/ADC12_IN15_25") (pintype "bidirectional"))
    )
    (net (code "79") (name "unconnected-(U1-PC6{slash}TIM3_CH1{slash}TIM_CH1{slash}USART6_TX(5T)-Pad37)") (class "Default")
      (node (ref "U1") (pin "37") (pinfunction "PC6/TIM3_CH1/TIM_CH1/USART6_TX(5T)_37") (pintype "bidirectional"))
    )
    (net (code "80") (name "unconnected-(U1-PC7{slash}TIM3_CH2{slash}TIM8_CH2{slash}USART6_RX(5T)-Pad38)") (class "Default")
      (node (ref "U1") (pin "38") (pinfunction "PC7/TIM3_CH2/TIM8_CH2/USART6_RX(5T)_38") (pintype "bidirectional"))
    )
    (net (code "81") (name "unconnected-(U1-PC8{slash}TIM3_CH3{slash}TIM8_CH3(5T)-Pad39)") (class "Default")
      (node (ref "U1") (pin "39") (pinfunction "PC8/TIM3_CH3/TIM8_CH3(5T)_39") (pintype "bidirectional"))
    )
    (net (code "82") (name "unconnected-(U1-PC9{slash}TIM3_CH4{slash}TIM8_CH4(5T)-Pad40)") (class "Default")
      (node (ref "U1") (pin "40") (pinfunction "PC9/TIM3_CH4/TIM8_CH4(5T)_40") (pintype "bidirectional"))
    )
    (net (code "83") (name "unconnected-(U1-PC10(5T)-Pad51)") (class "Default")
      (node (ref "U1") (pin "51") (pinfunction "PC10(5T)_51") (pintype "bidirectional"))
    )
    (net (code "84") (name "unconnected-(U1-PC11(5T)-Pad52)") (class "Default")
      (node (ref "U1") (pin "52") (pinfunction "PC11(5T)_52") (pintype "bidirectional"))
    )
    (net (code "85") (name "unconnected-(U1-PC12(5T)-Pad53)") (class "Default")
      (node (ref "U1") (pin "53") (pinfunction "PC12(5T)_53") (pintype "bidirectional"))
    )
    (net (code "86") (name "unconnected-(U1-PC13(5T)-Pad2)") (class "Default")
      (node (ref "U1") (pin "2") (pinfunction "PC13(5T)_2") (pintype "bidirectional"))
    )
    (net (code "87") (name "unconnected-(U1-PC14{slash}OSC32_IN(5T)-Pad3)") (class "Default")
      (node (ref "U1") (pin "3") (pinfunction "PC14/OSC32_IN(5T)_3") (pintype "bidirectional"))
    )
    (net (code "88") (name "unconnected-(U1-PC15{slash}OSC32_OUT(5T)-Pad4)") (class "Default")
      (node (ref "U1") (pin "4") (pinfunction "PC15/OSC32_OUT(5T)_4") (pintype "bidirectional"))
    )
    (net (code "89") (name "unconnected-(U1-PD2{slash}TIM3_ETR(5T)-Pad54)") (class "Default")
      (node (ref "U1") (pin "54") (pinfunction "PD2/TIM3_ETR(5T)_54") (pintype "bidirectional"))
    )
    (net (code "90") (name "unconnected-(U2-ALT-Pad5)") (class "Default")
      (node (ref "U2") (pin "5") (pinfunction "ALT_5") (pintype "bidirectional"))
    )
    (net (code "91") (name "unconnected-(U4-FLAG-Pad4)") (class "Default")
      (node (ref "U4") (pin "4") (pinfunction "FLAG_4") (pintype "bidirectional"))
    )
    (net (code "92") (name "unconnected-(U5-FLAG-Pad4)") (class "Default")
      (node (ref "U5") (pin "4") (pinfunction "FLAG_4") (pintype "bidirectional"))
    )
    (net (code "93") (name "unconnected-(U7-CTS-Pad12)") (class "Default")
      (node (ref "U7") (pin "12") (pinfunction "CTS_12") (pintype "output"))
    )
    (net (code "94") (name "unconnected-(U7-DIO0-Pad20)") (class "Default")
      (node (ref "U7") (pin "20") (pinfunction "DIO0_20") (pintype "bidirectional"))
    )
    (net (code "95") (name "unconnected-(U7-DIO1-Pad19)") (class "Default")
      (node (ref "U7") (pin "19") (pinfunction "DIO1_19") (pintype "bidirectional"))
    )
    (net (code "96") (name "unconnected-(U7-DIO2-Pad18)") (class "Default")
      (node (ref "U7") (pin "18") (pinfunction "DIO2_18") (pintype "bidirectional"))
    )
    (net (code "97") (name "unconnected-(U7-DIO3-Pad17)") (class "Default")
      (node (ref "U7") (pin "17") (pinfunction "DIO3_17") (pintype "bidirectional"))
    )
    (net (code "98") (name "unconnected-(U7-DIO4-Pad11)") (class "Default")
      (node (ref "U7") (pin "11") (pinfunction "DIO4_11") (pintype "bidirectional"))
    )
    (net (code "99") (name "unconnected-(U7-DIO5-Pad15)") (class "Default")
      (node (ref "U7") (pin "15") (pinfunction "DIO5_15") (pintype "bidirectional"))
    )
    (net (code "100") (name "unconnected-(U7-DIO9-Pad13)") (class "Default")
      (node (ref "U7") (pin "13") (pinfunction "DIO9_13") (pintype "bidirectional"))
    )
    (net (code "101") (name "unconnected-(U7-DIO11-Pad7)") (class "Default")
      (node (ref "U7") (pin "7") (pinfunction "DIO11_7") (pintype "bidirectional"))
    )
    (net (code "102") (name "unconnected-(U7-DIO12-Pad4)") (class "Default")
      (node (ref "U7") (pin "4") (pinfunction "DIO12_4") (pintype "bidirectional"))
    )
    (net (code "103") (name "unconnected-(U7-DTR-Pad9)") (class "Default")
      (node (ref "U7") (pin "9") (pinfunction "DTR_9") (pintype "bidirectional"))
    )
    (net (code "104") (name "unconnected-(U7-RES-Pad8)") (class "Default")
      (node (ref "U7") (pin "8") (pinfunction "RES_8") (pintype "bidirectional"))
    )
    (net (code "105") (name "unconnected-(U7-RES-Pad14)") (class "Default")
      (node (ref "U7") (pin "14") (pinfunction "RES_14") (pintype "bidirectional"))
    )
    (net (code "106") (name "unconnected-(U7-RSSI-Pad6)") (class "Default")
      (node (ref "U7") (pin "6") (pinfunction "RSSI_6") (pintype "bidirectional"))
    )
    (net (code "107") (name "unconnected-(U7-RTS-Pad16)") (class "Default")
      (node (ref "U7") (pin "16") (pinfunction "RTS_16") (pintype "input"))
    )
    (net (code "108") (name "unconnected-(U8-Pad3)") (class "Default")
      (node (ref "U8") (pin "3") (pinfunction "3_3") (pintype "passive"))
    )
    (net (code "109") (name "unconnected-(U8-Pad4)") (class "Default")
      (node (ref "U8") (pin "4") (pinfunction "4_4") (pintype "passive"))
    )
    (net (code "110") (name "unconnected-(U8-Pad5)") (class "Default")
      (node (ref "U8") (pin "5") (pinfunction "5_5") (pintype "passive"))
    )
    (net (code "111") (name "unconnected-(U8-Pad6)") (class "Default")
      (node (ref "U8") (pin "6") (pinfunction "6_6") (pintype "passive"))
    )
    (net (code "112") (name "unconnected-(U8-Pad7)") (class "Default")
      (node (ref "U8") (pin "7") (pinfunction "7_7") (pintype "passive"))
    )
    (net (code "113") (name "unconnected-(U8-Pad8)") (class "Default")
      (node (ref "U8") (pin "8") (pinfunction "8_8") (pintype "passive"))
    )
    (net (code "114") (name "unconnected-(U8-Pad9)") (class "Default")
      (node (ref "U8") (pin "9") (pinfunction "9_9") (pintype "passive"))
    )
    (net (code "115") (name "unconnected-(U8-Pad10)") (class "Default")
      (node (ref "U8") (pin "10") (pinfunction "10_10") (pintype "passive"))
    )
    (net (code "116") (name "unconnected-(U8-Pad11)") (class "Default")
      (node (ref "U8") (pin "11") (pinfunction "11_11") (pintype "passive"))
    )
    (net (code "117") (name "unconnected-(U8-Pad12)") (class "Default")
      (node (ref "U8") (pin "12") (pinfunction "12_12") (pintype "passive"))
    )
    (net (code "118") (name "unconnected-(U8-Pad14)") (class "Default")
      (node (ref "U8") (pin "14") (pinfunction "14_14") (pintype "passive"))
    )
    (net (code "119") (name "unconnected-(U8-Pad15)") (class "Default")
      (node (ref "U8") (pin "15") (pinfunction "15_15") (pintype "passive"))
    )
    (net (code "120") (name "unconnected-(U8-Pad16)") (class "Default")
      (node (ref "U8") (pin "16") (pinfunction "16_16") (pintype "passive"))
    )
    (net (code "121") (name "unconnected-(U8-Pad17)") (class "Default")
      (node (ref "U8") (pin "17") (pinfunction "17_17") (pintype "passive"))
    )
    (net (code "122") (name "unconnected-(U8-Pad18)") (class "Default")
      (node (ref "U8") (pin "18") (pinfunction "18_18") (pintype "passive"))
    )
    (net (code "123") (name "unconnected-(U8-Pad19)") (class "Default")
      (node (ref "U8") (pin "19") (pinfunction "19_19") (pintype "passive"))
    )
    (net (code "124") (name "unconnected-(U8-Pad22)") (class "Default")
      (node (ref "U8") (pin "22") (pinfunction "22_22") (pintype "passive"))
    )
    (net (code "125") (name "unconnected-(U8-Pad23)") (class "Default")
      (node (ref "U8") (pin "23") (pinfunction "23_23") (pintype "passive"))
    )
    (net (code "126") (name "unconnected-(U8-Pad24)") (class "Default")
      (node (ref "U8") (pin "24") (pinfunction "24_24") (pintype "passive"))
    )
  )
)
